# Page09_eMMC_QSPI.net
KiCad netlist of a schematic drawn in Altium Designer
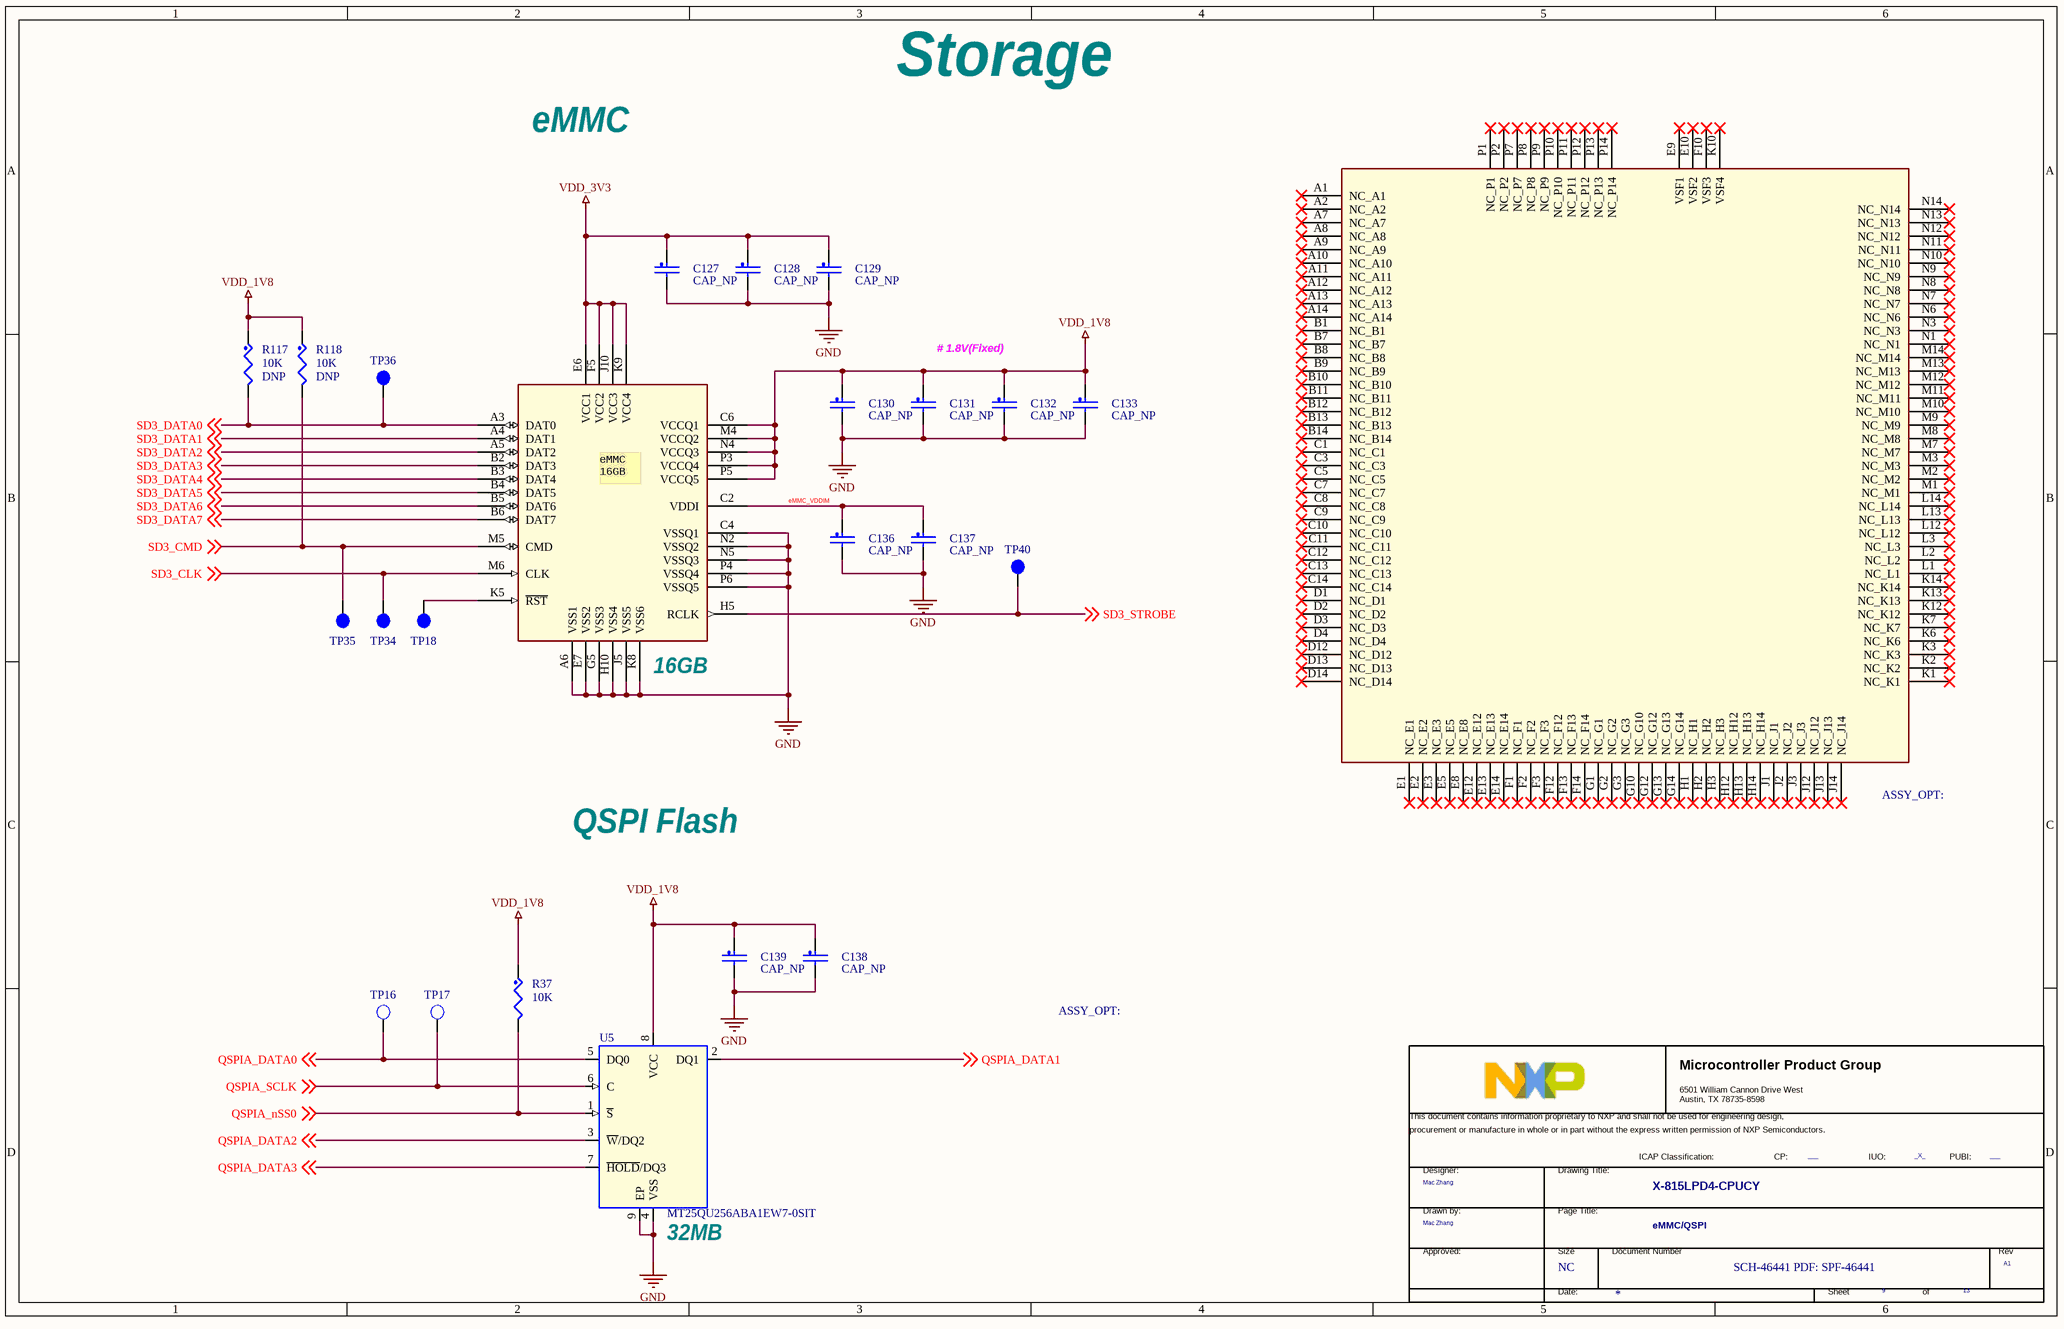
[diagram p0: Page09 eMMC_QSPI.SchDoc]

(export (version "E")
  (design (tool "Eeschema 10.0.6"))
  (components
    (comp (ref "C127") (value "CAP_NP") (footprint "RC0402") (libsource (lib "imx8mnano") (part "CAP_NP")))
    (comp (ref "C128") (value "CAP_NP") (footprint "RC0402") (libsource (lib "imx8mnano") (part "CAP_NP")))
    (comp (ref "C129") (value "CAP_NP") (footprint "RC0402") (libsource (lib "imx8mnano") (part "CAP_NP")))
    (comp (ref "C130") (value "CAP_NP") (footprint "RC0402") (libsource (lib "imx8mnano") (part "CAP_NP")))
    (comp (ref "C131") (value "CAP_NP") (footprint "RC0402") (libsource (lib "imx8mnano") (part "CAP_NP")))
    (comp (ref "C132") (value "CAP_NP") (footprint "RC0402") (libsource (lib "imx8mnano") (part "CAP_NP")))
    (comp (ref "C133") (value "CAP_NP") (footprint "RC0402") (libsource (lib "imx8mnano") (part "CAP_NP")))
    (comp (ref "C136") (value "CAP_NP") (footprint "RC0402") (libsource (lib "imx8mnano") (part "CAP_NP")))
    (comp (ref "C137") (value "CAP_NP") (footprint "RC0402") (libsource (lib "imx8mnano") (part "CAP_NP")))
    (comp (ref "C138") (value "CAP_NP") (footprint "RC0402") (libsource (lib "imx8mnano") (part "CAP_NP")))
    (comp (ref "C139") (value "CAP_NP") (footprint "RC0402") (libsource (lib "imx8mnano") (part "CAP_NP")))
    (comp (ref "R37")
      (value "10K")
      (footprint "0402_CC")
      (description "RES MF 10K 1/16W 5% 0402")
      (fields (field (name "TOLERANCE") "5%"))
      (libsource (lib "*") (part "RES"))
    )
    (comp (ref "R117")
      (value "10K")
      (footprint "0201_CC")
      (description "RES MF 10K 1/20W 5% 0201")
      (fields (field (name "ASSY_OPT") "DNP") (field (name "TOLERANCE") "5%"))
      (libsource (lib "*") (part "RES"))
    )
    (comp (ref "R118")
      (value "10K")
      (footprint "0201_CC")
      (description "RES MF 10K 1/20W 5% 0201")
      (fields (field (name "ASSY_OPT") "DNP") (field (name "TOLERANCE") "5%"))
      (libsource (lib "*") (part "RES"))
    )
    (comp (ref "TP16")
      (value "TP_35MIL")
      (footprint "testpoint_35mil")
      (description "TEST POINT PAD .035 SMT, no part to order")
      (libsource (lib "*") (part "T POINT R"))
    )
    (comp (ref "TP17")
      (value "TP_35MIL")
      (footprint "testpoint_35mil")
      (description "TEST POINT PAD .035 SMT, no part to order")
      (libsource (lib "*") (part "T POINT R"))
    )
    (comp (ref "TP18")
      (value "tpad_020")
      (footprint "tpad_020")
      (description "TEST POINT PAD 0.5MM DIA SMT, NO PART TO ORDER")
      (libsource (lib "*") (part "TESTLOOP"))
    )
    (comp (ref "TP34")
      (value "tpad_020")
      (footprint "tpad_020")
      (description "TEST POINT PAD 0.5MM DIA SMT, NO PART TO ORDER")
      (libsource (lib "*") (part "TESTLOOP"))
    )
    (comp (ref "TP35")
      (value "TPAD_015")
      (footprint "TPAD_015")
      (description "TEST POINT PAD 15MIL DIA SMT, NO PART TO ORDER")
      (libsource (lib "*") (part "TESTLOOP"))
    )
    (comp (ref "TP36")
      (value "tpad_020")
      (footprint "tpad_020")
      (description "TEST POINT PAD 0.5MM DIA SMT, NO PART TO ORDER")
      (libsource (lib "*") (part "TESTLOOP"))
    )
    (comp (ref "TP40")
      (value "TPAD_015")
      (footprint "TPAD_015")
      (description "TEST POINT PAD 15MIL DIA SMT, NO PART TO ORDER")
      (libsource (lib "*") (part "TESTLOOP"))
    )
    (comp (ref "U4")
      (value "SDINBDG4-16G_VFBGA_153P")
      (footprint "BGA153N50P14X14_1300X1150X80")
      (libsource (lib "imx8mnano") (part "SDINBDG4-16G_VFBGA_153P"))
    )
    (comp (ref "U5")
      (value "MT25QU256ABA1EW7-0SIT")
      (footprint "dfn8_1p27_6x5mm_3p1")
      (description "IC MEM FLASH SERIAL NOR 256MBIT 166MHZ 1.7-2V WPDFN8")
      (fields (field (name "VOLTAGE") "1.7-2V"))
      (libsource (lib "*") (part "MT25QL256ABA1EW9_9P"))
    )
  )
  (nets
    (net (code "1") (name "/eMMC_VDDIM") (class "Default")
      (node (ref "C136") (pin "1") (pinfunction "1_1") (pintype "passive"))
      (node (ref "C137") (pin "1") (pinfunction "1_1") (pintype "passive"))
      (node (ref "U4") (pin "C2") (pinfunction "VDDI_C2") (pintype "power_in"))
    )
    (net (code "2") (name "GND") (class "Default")
      (node (ref "C127") (pin "2") (pinfunction "2_2") (pintype "passive"))
      (node (ref "C128") (pin "2") (pinfunction "2_2") (pintype "passive"))
      (node (ref "C129") (pin "2") (pinfunction "2_2") (pintype "passive"))
      (node (ref "C130") (pin "2") (pinfunction "2_2") (pintype "passive"))
      (node (ref "C131") (pin "2") (pinfunction "2_2") (pintype "passive"))
      (node (ref "C132") (pin "2") (pinfunction "2_2") (pintype "passive"))
      (node (ref "C133") (pin "2") (pinfunction "2_2") (pintype "passive"))
      (node (ref "C136") (pin "2") (pinfunction "2_2") (pintype "passive"))
      (node (ref "C137") (pin "2") (pinfunction "2_2") (pintype "passive"))
      (node (ref "C138") (pin "2") (pinfunction "2_2") (pintype "passive"))
      (node (ref "C139") (pin "2") (pinfunction "2_2") (pintype "passive"))
      (node (ref "U4") (pin "A6") (pinfunction "VSS1_A6") (pintype "power_in"))
      (node (ref "U4") (pin "C4") (pinfunction "VSSQ1_C4") (pintype "power_in"))
      (node (ref "U4") (pin "E7") (pinfunction "VSS2_E7") (pintype "power_in"))
      (node (ref "U4") (pin "G5") (pinfunction "VSS3_G5") (pintype "power_in"))
      (node (ref "U4") (pin "H10") (pinfunction "VSS4_H10") (pintype "power_in"))
      (node (ref "U4") (pin "J5") (pinfunction "VSS5_J5") (pintype "power_in"))
      (node (ref "U4") (pin "K8") (pinfunction "VSS6_K8") (pintype "power_in"))
      (node (ref "U4") (pin "N2") (pinfunction "VSSQ2_N2") (pintype "power_in"))
      (node (ref "U4") (pin "N5") (pinfunction "VSSQ3_N5") (pintype "power_in"))
      (node (ref "U4") (pin "P4") (pinfunction "VSSQ4_P4") (pintype "power_in"))
      (node (ref "U4") (pin "P6") (pinfunction "VSSQ5_P6") (pintype "power_in"))
      (node (ref "U5") (pin "4") (pinfunction "VSS_4") (pintype "power_in"))
      (node (ref "U5") (pin "9") (pinfunction "EP_9") (pintype "power_in"))
    )
    (net (code "3") (name "Net-(TP18-Pin1)") (class "Default")
      (node (ref "TP18") (pin "1") (pinfunction "Pin1_1") (pintype "passive"))
      (node (ref "U4") (pin "K5") (pinfunction "~{RST}_K5") (pintype "input"))
    )
    (net (code "4") (name "QSPIA_DATA0") (class "Default")
      (node (ref "TP16") (pin "1") (pinfunction "TP_1") (pintype "passive"))
      (node (ref "U5") (pin "5") (pinfunction "DQ0_5") (pintype "bidirectional"))
    )
    (net (code "5") (name "QSPIA_DATA1") (class "Default")
      (node (ref "U5") (pin "2") (pinfunction "DQ1_2") (pintype "bidirectional"))
    )
    (net (code "6") (name "QSPIA_DATA2") (class "Default")
      (node (ref "U5") (pin "3") (pinfunction "~{W}/DQ2_3") (pintype "bidirectional"))
    )
    (net (code "7") (name "QSPIA_DATA3") (class "Default")
      (node (ref "U5") (pin "7") (pinfunction "~{HOLD}/DQ3_7") (pintype "bidirectional"))
    )
    (net (code "8") (name "QSPIA_SCLK") (class "Default")
      (node (ref "TP17") (pin "1") (pinfunction "TP_1") (pintype "passive"))
      (node (ref "U5") (pin "6") (pinfunction "C_6") (pintype "input"))
    )
    (net (code "9") (name "QSPIA_nSS0") (class "Default")
      (node (ref "R37") (pin "2") (pinfunction "2_2") (pintype "passive"))
      (node (ref "U5") (pin "1") (pinfunction "~{S}_1") (pintype "input"))
    )
    (net (code "10") (name "SD3_CLK") (class "Default")
      (node (ref "TP34") (pin "1") (pinfunction "Pin1_1") (pintype "passive"))
      (node (ref "U4") (pin "M6") (pinfunction "CLK_M6") (pintype "input"))
    )
    (net (code "11") (name "SD3_CMD") (class "Default")
      (node (ref "R118") (pin "2") (pinfunction "2_2") (pintype "passive"))
      (node (ref "TP35") (pin "1") (pinfunction "Pin1_1") (pintype "passive"))
      (node (ref "U4") (pin "M5") (pinfunction "CMD_M5") (pintype "bidirectional"))
    )
    (net (code "12") (name "SD3_DATA0") (class "Default")
      (node (ref "R117") (pin "2") (pinfunction "2_2") (pintype "passive"))
      (node (ref "TP36") (pin "1") (pinfunction "Pin1_1") (pintype "passive"))
      (node (ref "U4") (pin "A3") (pinfunction "DAT0_A3") (pintype "bidirectional"))
    )
    (net (code "13") (name "SD3_DATA1") (class "Default")
      (node (ref "U4") (pin "A4") (pinfunction "DAT1_A4") (pintype "bidirectional"))
    )
    (net (code "14") (name "SD3_DATA2") (class "Default")
      (node (ref "U4") (pin "A5") (pinfunction "DAT2_A5") (pintype "bidirectional"))
    )
    (net (code "15") (name "SD3_DATA3") (class "Default")
      (node (ref "U4") (pin "B2") (pinfunction "DAT3_B2") (pintype "bidirectional"))
    )
    (net (code "16") (name "SD3_DATA4") (class "Default")
      (node (ref "U4") (pin "B3") (pinfunction "DAT4_B3") (pintype "bidirectional"))
    )
    (net (code "17") (name "SD3_DATA5") (class "Default")
      (node (ref "U4") (pin "B4") (pinfunction "DAT5_B4") (pintype "bidirectional"))
    )
    (net (code "18") (name "SD3_DATA6") (class "Default")
      (node (ref "U4") (pin "B5") (pinfunction "DAT6_B5") (pintype "bidirectional"))
    )
    (net (code "19") (name "SD3_DATA7") (class "Default")
      (node (ref "U4") (pin "B6") (pinfunction "DAT7_B6") (pintype "bidirectional"))
    )
    (net (code "20") (name "SD3_STROBE") (class "Default")
      (node (ref "TP40") (pin "1") (pinfunction "Pin1_1") (pintype "passive"))
      (node (ref "U4") (pin "H5") (pinfunction "RCLK_H5") (pintype "output"))
    )
    (net (code "21") (name "VDD_1V8") (class "Default")
      (node (ref "C130") (pin "1") (pinfunction "1_1") (pintype "passive"))
      (node (ref "C131") (pin "1") (pinfunction "1_1") (pintype "passive"))
      (node (ref "C132") (pin "1") (pinfunction "1_1") (pintype "passive"))
      (node (ref "C133") (pin "1") (pinfunction "1_1") (pintype "passive"))
      (node (ref "C138") (pin "1") (pinfunction "1_1") (pintype "passive"))
      (node (ref "C139") (pin "1") (pinfunction "1_1") (pintype "passive"))
      (node (ref "R117") (pin "1") (pinfunction "1_1") (pintype "passive"))
      (node (ref "R118") (pin "1") (pinfunction "1_1") (pintype "passive"))
      (node (ref "R37") (pin "1") (pinfunction "1_1") (pintype "passive"))
      (node (ref "U4") (pin "C6") (pinfunction "VCCQ1_C6") (pintype "power_in"))
      (node (ref "U4") (pin "M4") (pinfunction "VCCQ2_M4") (pintype "power_in"))
      (node (ref "U4") (pin "N4") (pinfunction "VCCQ3_N4") (pintype "power_in"))
      (node (ref "U4") (pin "P3") (pinfunction "VCCQ4_P3") (pintype "power_in"))
      (node (ref "U4") (pin "P5") (pinfunction "VCCQ5_P5") (pintype "power_in"))
      (node (ref "U5") (pin "8") (pinfunction "VCC_8") (pintype "power_in"))
    )
    (net (code "22") (name "VDD_3V3") (class "Default")
      (node (ref "C127") (pin "1") (pinfunction "1_1") (pintype "passive"))
      (node (ref "C128") (pin "1") (pinfunction "1_1") (pintype "passive"))
      (node (ref "C129") (pin "1") (pinfunction "1_1") (pintype "passive"))
      (node (ref "U4") (pin "E6") (pinfunction "VCC1_E6") (pintype "power_in"))
      (node (ref "U4") (pin "F5") (pinfunction "VCC2_F5") (pintype "power_in"))
      (node (ref "U4") (pin "J10") (pinfunction "VCC3_J10") (pintype "power_in"))
      (node (ref "U4") (pin "K9") (pinfunction "VCC4_K9") (pintype "power_in"))
    )
    (net (code "23") (name "unconnected-(U4B-NC_A1-PadA1)") (class "Default")
      (node (ref "U4") (pin "A1") (pinfunction "NC_A1_A1") (pintype "passive+no_connect"))
    )
    (net (code "24") (name "unconnected-(U4B-NC_A2-PadA2)") (class "Default")
      (node (ref "U4") (pin "A2") (pinfunction "NC_A2_A2") (pintype "passive+no_connect"))
    )
    (net (code "25") (name "unconnected-(U4B-NC_A7-PadA7)") (class "Default")
      (node (ref "U4") (pin "A7") (pinfunction "NC_A7_A7") (pintype "passive+no_connect"))
    )
    (net (code "26") (name "unconnected-(U4B-NC_A8-PadA8)") (class "Default")
      (node (ref "U4") (pin "A8") (pinfunction "NC_A8_A8") (pintype "passive+no_connect"))
    )
    (net (code "27") (name "unconnected-(U4B-NC_A9-PadA9)") (class "Default")
      (node (ref "U4") (pin "A9") (pinfunction "NC_A9_A9") (pintype "passive+no_connect"))
    )
    (net (code "28") (name "unconnected-(U4B-NC_A10-PadA10)") (class "Default")
      (node (ref "U4") (pin "A10") (pinfunction "NC_A10_A10") (pintype "passive+no_connect"))
    )
    (net (code "29") (name "unconnected-(U4B-NC_A11-PadA11)") (class "Default")
      (node (ref "U4") (pin "A11") (pinfunction "NC_A11_A11") (pintype "passive+no_connect"))
    )
    (net (code "30") (name "unconnected-(U4B-NC_A12-PadA12)") (class "Default")
      (node (ref "U4") (pin "A12") (pinfunction "NC_A12_A12") (pintype "passive+no_connect"))
    )
    (net (code "31") (name "unconnected-(U4B-NC_A13-PadA13)") (class "Default")
      (node (ref "U4") (pin "A13") (pinfunction "NC_A13_A13") (pintype "passive+no_connect"))
    )
    (net (code "32") (name "unconnected-(U4B-NC_A14-PadA14)") (class "Default")
      (node (ref "U4") (pin "A14") (pinfunction "NC_A14_A14") (pintype "passive+no_connect"))
    )
    (net (code "33") (name "unconnected-(U4B-NC_B1-PadB1)") (class "Default")
      (node (ref "U4") (pin "B1") (pinfunction "NC_B1_B1") (pintype "passive+no_connect"))
    )
    (net (code "34") (name "unconnected-(U4B-NC_B7-PadB7)") (class "Default")
      (node (ref "U4") (pin "B7") (pinfunction "NC_B7_B7") (pintype "passive+no_connect"))
    )
    (net (code "35") (name "unconnected-(U4B-NC_B8-PadB8)") (class "Default")
      (node (ref "U4") (pin "B8") (pinfunction "NC_B8_B8") (pintype "passive+no_connect"))
    )
    (net (code "36") (name "unconnected-(U4B-NC_B9-PadB9)") (class "Default")
      (node (ref "U4") (pin "B9") (pinfunction "NC_B9_B9") (pintype "passive+no_connect"))
    )
    (net (code "37") (name "unconnected-(U4B-NC_B10-PadB10)") (class "Default")
      (node (ref "U4") (pin "B10") (pinfunction "NC_B10_B10") (pintype "passive+no_connect"))
    )
    (net (code "38") (name "unconnected-(U4B-NC_B11-PadB11)") (class "Default")
      (node (ref "U4") (pin "B11") (pinfunction "NC_B11_B11") (pintype "passive+no_connect"))
    )
    (net (code "39") (name "unconnected-(U4B-NC_B12-PadB12)") (class "Default")
      (node (ref "U4") (pin "B12") (pinfunction "NC_B12_B12") (pintype "passive+no_connect"))
    )
    (net (code "40") (name "unconnected-(U4B-NC_B13-PadB13)") (class "Default")
      (node (ref "U4") (pin "B13") (pinfunction "NC_B13_B13") (pintype "passive+no_connect"))
    )
    (net (code "41") (name "unconnected-(U4B-NC_B14-PadB14)") (class "Default")
      (node (ref "U4") (pin "B14") (pinfunction "NC_B14_B14") (pintype "passive+no_connect"))
    )
    (net (code "42") (name "unconnected-(U4B-NC_C1-PadC1)") (class "Default")
      (node (ref "U4") (pin "C1") (pinfunction "NC_C1_C1") (pintype "passive+no_connect"))
    )
    (net (code "43") (name "unconnected-(U4B-NC_C3-PadC3)") (class "Default")
      (node (ref "U4") (pin "C3") (pinfunction "NC_C3_C3") (pintype "passive+no_connect"))
    )
    (net (code "44") (name "unconnected-(U4B-NC_C5-PadC5)") (class "Default")
      (node (ref "U4") (pin "C5") (pinfunction "NC_C5_C5") (pintype "passive+no_connect"))
    )
    (net (code "45") (name "unconnected-(U4B-NC_C7-PadC7)") (class "Default")
      (node (ref "U4") (pin "C7") (pinfunction "NC_C7_C7") (pintype "passive+no_connect"))
    )
    (net (code "46") (name "unconnected-(U4B-NC_C8-PadC8)") (class "Default")
      (node (ref "U4") (pin "C8") (pinfunction "NC_C8_C8") (pintype "passive+no_connect"))
    )
    (net (code "47") (name "unconnected-(U4B-NC_C9-PadC9)") (class "Default")
      (node (ref "U4") (pin "C9") (pinfunction "NC_C9_C9") (pintype "passive+no_connect"))
    )
    (net (code "48") (name "unconnected-(U4B-NC_C10-PadC10)") (class "Default")
      (node (ref "U4") (pin "C10") (pinfunction "NC_C10_C10") (pintype "passive+no_connect"))
    )
    (net (code "49") (name "unconnected-(U4B-NC_C11-PadC11)") (class "Default")
      (node (ref "U4") (pin "C11") (pinfunction "NC_C11_C11") (pintype "passive+no_connect"))
    )
    (net (code "50") (name "unconnected-(U4B-NC_C12-PadC12)") (class "Default")
      (node (ref "U4") (pin "C12") (pinfunction "NC_C12_C12") (pintype "passive+no_connect"))
    )
    (net (code "51") (name "unconnected-(U4B-NC_C13-PadC13)") (class "Default")
      (node (ref "U4") (pin "C13") (pinfunction "NC_C13_C13") (pintype "passive+no_connect"))
    )
    (net (code "52") (name "unconnected-(U4B-NC_C14-PadC14)") (class "Default")
      (node (ref "U4") (pin "C14") (pinfunction "NC_C14_C14") (pintype "passive+no_connect"))
    )
    (net (code "53") (name "unconnected-(U4B-NC_D1-PadD1)") (class "Default")
      (node (ref "U4") (pin "D1") (pinfunction "NC_D1_D1") (pintype "passive+no_connect"))
    )
    (net (code "54") (name "unconnected-(U4B-NC_D2-PadD2)") (class "Default")
      (node (ref "U4") (pin "D2") (pinfunction "NC_D2_D2") (pintype "passive+no_connect"))
    )
    (net (code "55") (name "unconnected-(U4B-NC_D3-PadD3)") (class "Default")
      (node (ref "U4") (pin "D3") (pinfunction "NC_D3_D3") (pintype "passive+no_connect"))
    )
    (net (code "56") (name "unconnected-(U4B-NC_D4-PadD4)") (class "Default")
      (node (ref "U4") (pin "D4") (pinfunction "NC_D4_D4") (pintype "passive+no_connect"))
    )
    (net (code "57") (name "unconnected-(U4B-NC_D12-PadD12)") (class "Default")
      (node (ref "U4") (pin "D12") (pinfunction "NC_D12_D12") (pintype "passive+no_connect"))
    )
    (net (code "58") (name "unconnected-(U4B-NC_D13-PadD13)") (class "Default")
      (node (ref "U4") (pin "D13") (pinfunction "NC_D13_D13") (pintype "passive+no_connect"))
    )
    (net (code "59") (name "unconnected-(U4B-NC_D14-PadD14)") (class "Default")
      (node (ref "U4") (pin "D14") (pinfunction "NC_D14_D14") (pintype "passive+no_connect"))
    )
    (net (code "60") (name "unconnected-(U4B-NC_E1-PadE1)") (class "Default")
      (node (ref "U4") (pin "E1") (pinfunction "NC_E1_E1") (pintype "passive+no_connect"))
    )
    (net (code "61") (name "unconnected-(U4B-NC_E2-PadE2)") (class "Default")
      (node (ref "U4") (pin "E2") (pinfunction "NC_E2_E2") (pintype "passive+no_connect"))
    )
    (net (code "62") (name "unconnected-(U4B-NC_E3-PadE3)") (class "Default")
      (node (ref "U4") (pin "E3") (pinfunction "NC_E3_E3") (pintype "passive+no_connect"))
    )
    (net (code "63") (name "unconnected-(U4B-NC_E5-PadE5)") (class "Default")
      (node (ref "U4") (pin "E5") (pinfunction "NC_E5_E5") (pintype "passive+no_connect"))
    )
    (net (code "64") (name "unconnected-(U4B-NC_E8-PadE8)") (class "Default")
      (node (ref "U4") (pin "E8") (pinfunction "NC_E8_E8") (pintype "passive+no_connect"))
    )
    (net (code "65") (name "unconnected-(U4B-NC_E12-PadE12)") (class "Default")
      (node (ref "U4") (pin "E12") (pinfunction "NC_E12_E12") (pintype "passive+no_connect"))
    )
    (net (code "66") (name "unconnected-(U4B-NC_E13-PadE13)") (class "Default")
      (node (ref "U4") (pin "E13") (pinfunction "NC_E13_E13") (pintype "passive+no_connect"))
    )
    (net (code "67") (name "unconnected-(U4B-NC_E14-PadE14)") (class "Default")
      (node (ref "U4") (pin "E14") (pinfunction "NC_E14_E14") (pintype "passive+no_connect"))
    )
    (net (code "68") (name "unconnected-(U4B-NC_F1-PadF1)") (class "Default")
      (node (ref "U4") (pin "F1") (pinfunction "NC_F1_F1") (pintype "passive+no_connect"))
    )
    (net (code "69") (name "unconnected-(U4B-NC_F2-PadF2)") (class "Default")
      (node (ref "U4") (pin "F2") (pinfunction "NC_F2_F2") (pintype "passive+no_connect"))
    )
    (net (code "70") (name "unconnected-(U4B-NC_F3-PadF3)") (class "Default")
      (node (ref "U4") (pin "F3") (pinfunction "NC_F3_F3") (pintype "passive+no_connect"))
    )
    (net (code "71") (name "unconnected-(U4B-NC_F12-PadF12)") (class "Default")
      (node (ref "U4") (pin "F12") (pinfunction "NC_F12_F12") (pintype "passive+no_connect"))
    )
    (net (code "72") (name "unconnected-(U4B-NC_F13-PadF13)") (class "Default")
      (node (ref "U4") (pin "F13") (pinfunction "NC_F13_F13") (pintype "passive+no_connect"))
    )
    (net (code "73") (name "unconnected-(U4B-NC_F14-PadF14)") (class "Default")
      (node (ref "U4") (pin "F14") (pinfunction "NC_F14_F14") (pintype "passive+no_connect"))
    )
    (net (code "74") (name "unconnected-(U4B-NC_G1-PadG1)") (class "Default")
      (node (ref "U4") (pin "G1") (pinfunction "NC_G1_G1") (pintype "passive+no_connect"))
    )
    (net (code "75") (name "unconnected-(U4B-NC_G2-PadG2)") (class "Default")
      (node (ref "U4") (pin "G2") (pinfunction "NC_G2_G2") (pintype "passive+no_connect"))
    )
    (net (code "76") (name "unconnected-(U4B-NC_G3-PadG3)") (class "Default")
      (node (ref "U4") (pin "G3") (pinfunction "NC_G3_G3") (pintype "passive+no_connect"))
    )
    (net (code "77") (name "unconnected-(U4B-NC_G10-PadG10)") (class "Default")
      (node (ref "U4") (pin "G10") (pinfunction "NC_G10_G10") (pintype "passive+no_connect"))
    )
    (net (code "78") (name "unconnected-(U4B-NC_G12-PadG12)") (class "Default")
      (node (ref "U4") (pin "G12") (pinfunction "NC_G12_G12") (pintype "passive+no_connect"))
    )
    (net (code "79") (name "unconnected-(U4B-NC_G13-PadG13)") (class "Default")
      (node (ref "U4") (pin "G13") (pinfunction "NC_G13_G13") (pintype "passive+no_connect"))
    )
    (net (code "80") (name "unconnected-(U4B-NC_G14-PadG14)") (class "Default")
      (node (ref "U4") (pin "G14") (pinfunction "NC_G14_G14") (pintype "passive+no_connect"))
    )
    (net (code "81") (name "unconnected-(U4B-NC_H1-PadH1)") (class "Default")
      (node (ref "U4") (pin "H1") (pinfunction "NC_H1_H1") (pintype "passive+no_connect"))
    )
    (net (code "82") (name "unconnected-(U4B-NC_H2-PadH2)") (class "Default")
      (node (ref "U4") (pin "H2") (pinfunction "NC_H2_H2") (pintype "passive+no_connect"))
    )
    (net (code "83") (name "unconnected-(U4B-NC_H3-PadH3)") (class "Default")
      (node (ref "U4") (pin "H3") (pinfunction "NC_H3_H3") (pintype "passive+no_connect"))
    )
    (net (code "84") (name "unconnected-(U4B-NC_H12-PadH12)") (class "Default")
      (node (ref "U4") (pin "H12") (pinfunction "NC_H12_H12") (pintype "passive+no_connect"))
    )
    (net (code "85") (name "unconnected-(U4B-NC_H13-PadH13)") (class "Default")
      (node (ref "U4") (pin "H13") (pinfunction "NC_H13_H13") (pintype "passive+no_connect"))
    )
    (net (code "86") (name "unconnected-(U4B-NC_H14-PadH14)") (class "Default")
      (node (ref "U4") (pin "H14") (pinfunction "NC_H14_H14") (pintype "passive+no_connect"))
    )
    (net (code "87") (name "unconnected-(U4B-NC_J1-PadJ1)") (class "Default")
      (node (ref "U4") (pin "J1") (pinfunction "NC_J1_J1") (pintype "passive+no_connect"))
    )
    (net (code "88") (name "unconnected-(U4B-NC_J2-PadJ2)") (class "Default")
      (node (ref "U4") (pin "J2") (pinfunction "NC_J2_J2") (pintype "passive+no_connect"))
    )
    (net (code "89") (name "unconnected-(U4B-NC_J3-PadJ3)") (class "Default")
      (node (ref "U4") (pin "J3") (pinfunction "NC_J3_J3") (pintype "passive+no_connect"))
    )
    (net (code "90") (name "unconnected-(U4B-NC_J12-PadJ12)") (class "Default")
      (node (ref "U4") (pin "J12") (pinfunction "NC_J12_J12") (pintype "passive+no_connect"))
    )
    (net (code "91") (name "unconnected-(U4B-NC_J13-PadJ13)") (class "Default")
      (node (ref "U4") (pin "J13") (pinfunction "NC_J13_J13") (pintype "passive+no_connect"))
    )
    (net (code "92") (name "unconnected-(U4B-NC_J14-PadJ14)") (class "Default")
      (node (ref "U4") (pin "J14") (pinfunction "NC_J14_J14") (pintype "passive+no_connect"))
    )
    (net (code "93") (name "unconnected-(U4B-NC_K1-PadK1)") (class "Default")
      (node (ref "U4") (pin "K1") (pinfunction "NC_K1_K1") (pintype "passive+no_connect"))
    )
    (net (code "94") (name "unconnected-(U4B-NC_K2-PadK2)") (class "Default")
      (node (ref "U4") (pin "K2") (pinfunction "NC_K2_K2") (pintype "passive+no_connect"))
    )
    (net (code "95") (name "unconnected-(U4B-NC_K3-PadK3)") (class "Default")
      (node (ref "U4") (pin "K3") (pinfunction "NC_K3_K3") (pintype "passive+no_connect"))
    )
    (net (code "96") (name "unconnected-(U4B-NC_K6-PadK6)") (class "Default")
      (node (ref "U4") (pin "K6") (pinfunction "NC_K6_K6") (pintype "passive+no_connect"))
    )
    (net (code "97") (name "unconnected-(U4B-NC_K7-PadK7)") (class "Default")
      (node (ref "U4") (pin "K7") (pinfunction "NC_K7_K7") (pintype "passive+no_connect"))
    )
    (net (code "98") (name "unconnected-(U4B-NC_K12-PadK12)") (class "Default")
      (node (ref "U4") (pin "K12") (pinfunction "NC_K12_K12") (pintype "passive+no_connect"))
    )
    (net (code "99") (name "unconnected-(U4B-NC_K13-PadK13)") (class "Default")
      (node (ref "U4") (pin "K13") (pinfunction "NC_K13_K13") (pintype "passive+no_connect"))
    )
    (net (code "100") (name "unconnected-(U4B-NC_K14-PadK14)") (class "Default")
      (node (ref "U4") (pin "K14") (pinfunction "NC_K14_K14") (pintype "passive+no_connect"))
    )
    (net (code "101") (name "unconnected-(U4B-NC_L1-PadL1)") (class "Default")
      (node (ref "U4") (pin "L1") (pinfunction "NC_L1_L1") (pintype "passive+no_connect"))
    )
    (net (code "102") (name "unconnected-(U4B-NC_L2-PadL2)") (class "Default")
      (node (ref "U4") (pin "L2") (pinfunction "NC_L2_L2") (pintype "passive+no_connect"))
    )
    (net (code "103") (name "unconnected-(U4B-NC_L3-PadL3)") (class "Default")
      (node (ref "U4") (pin "L3") (pinfunction "NC_L3_L3") (pintype "passive+no_connect"))
    )
    (net (code "104") (name "unconnected-(U4B-NC_L12-PadL12)") (class "Default")
      (node (ref "U4") (pin "L12") (pinfunction "NC_L12_L12") (pintype "passive+no_connect"))
    )
    (net (code "105") (name "unconnected-(U4B-NC_L13-PadL13)") (class "Default")
      (node (ref "U4") (pin "L13") (pinfunction "NC_L13_L13") (pintype "passive+no_connect"))
    )
    (net (code "106") (name "unconnected-(U4B-NC_L14-PadL14)") (class "Default")
      (node (ref "U4") (pin "L14") (pinfunction "NC_L14_L14") (pintype "passive+no_connect"))
    )
    (net (code "107") (name "unconnected-(U4B-NC_M1-PadM1)") (class "Default")
      (node (ref "U4") (pin "M1") (pinfunction "NC_M1_M1") (pintype "passive+no_connect"))
    )
    (net (code "108") (name "unconnected-(U4B-NC_M2-PadM2)") (class "Default")
      (node (ref "U4") (pin "M2") (pinfunction "NC_M2_M2") (pintype "passive+no_connect"))
    )
    (net (code "109") (name "unconnected-(U4B-NC_M3-PadM3)") (class "Default")
      (node (ref "U4") (pin "M3") (pinfunction "NC_M3_M3") (pintype "passive+no_connect"))
    )
    (net (code "110") (name "unconnected-(U4B-NC_M7-PadM7)") (class "Default")
      (node (ref "U4") (pin "M7") (pinfunction "NC_M7_M7") (pintype "passive+no_connect"))
    )
    (net (code "111") (name "unconnected-(U4B-NC_M8-PadM8)") (class "Default")
      (node (ref "U4") (pin "M8") (pinfunction "NC_M8_M8") (pintype "passive+no_connect"))
    )
    (net (code "112") (name "unconnected-(U4B-NC_M9-PadM9)") (class "Default")
      (node (ref "U4") (pin "M9") (pinfunction "NC_M9_M9") (pintype "passive+no_connect"))
    )
    (net (code "113") (name "unconnected-(U4B-NC_M10-PadM10)") (class "Default")
      (node (ref "U4") (pin "M10") (pinfunction "NC_M10_M10") (pintype "passive+no_connect"))
    )
    (net (code "114") (name "unconnected-(U4B-NC_M11-PadM11)") (class "Default")
      (node (ref "U4") (pin "M11") (pinfunction "NC_M11_M11") (pintype "passive+no_connect"))
    )
    (net (code "115") (name "unconnected-(U4B-NC_M12-PadM12)") (class "Default")
      (node (ref "U4") (pin "M12") (pinfunction "NC_M12_M12") (pintype "passive+no_connect"))
    )
    (net (code "116") (name "unconnected-(U4B-NC_M13-PadM13)") (class "Default")
      (node (ref "U4") (pin "M13") (pinfunction "NC_M13_M13") (pintype "passive+no_connect"))
    )
    (net (code "117") (name "unconnected-(U4B-NC_M14-PadM14)") (class "Default")
      (node (ref "U4") (pin "M14") (pinfunction "NC_M14_M14") (pintype "passive+no_connect"))
    )
    (net (code "118") (name "unconnected-(U4B-NC_N1-PadN1)") (class "Default")
      (node (ref "U4") (pin "N1") (pinfunction "NC_N1_N1") (pintype "passive+no_connect"))
    )
    (net (code "119") (name "unconnected-(U4B-NC_N3-PadN3)") (class "Default")
      (node (ref "U4") (pin "N3") (pinfunction "NC_N3_N3") (pintype "passive+no_connect"))
    )
    (net (code "120") (name "unconnected-(U4B-NC_N6-PadN6)") (class "Default")
      (node (ref "U4") (pin "N6") (pinfunction "NC_N6_N6") (pintype "passive+no_connect"))
    )
    (net (code "121") (name "unconnected-(U4B-NC_N7-PadN7)") (class "Default")
      (node (ref "U4") (pin "N7") (pinfunction "NC_N7_N7") (pintype "passive+no_connect"))
    )
    (net (code "122") (name "unconnected-(U4B-NC_N8-PadN8)") (class "Default")
      (node (ref "U4") (pin "N8") (pinfunction "NC_N8_N8") (pintype "passive+no_connect"))
    )
    (net (code "123") (name "unconnected-(U4B-NC_N9-PadN9)") (class "Default")
      (node (ref "U4") (pin "N9") (pinfunction "NC_N9_N9") (pintype "passive+no_connect"))
    )
    (net (code "124") (name "unconnected-(U4B-NC_N10-PadN10)") (class "Default")
      (node (ref "U4") (pin "N10") (pinfunction "NC_N10_N10") (pintype "passive+no_connect"))
    )
    (net (code "125") (name "unconnected-(U4B-NC_N11-PadN11)") (class "Default")
      (node (ref "U4") (pin "N11") (pinfunction "NC_N11_N11") (pintype "passive+no_connect"))
    )
    (net (code "126") (name "unconnected-(U4B-NC_N12-PadN12)") (class "Default")
      (node (ref "U4") (pin "N12") (pinfunction "NC_N12_N12") (pintype "passive+no_connect"))
    )
    (net (code "127") (name "unconnected-(U4B-NC_N13-PadN13)") (class "Default")
      (node (ref "U4") (pin "N13") (pinfunction "NC_N13_N13") (pintype "passive+no_connect"))
    )
    (net (code "128") (name "unconnected-(U4B-NC_N14-PadN14)") (class "Default")
      (node (ref "U4") (pin "N14") (pinfunction "NC_N14_N14") (pintype "passive+no_connect"))
    )
    (net (code "129") (name "unconnected-(U4B-NC_P1-PadP1)") (class "Default")
      (node (ref "U4") (pin "P1") (pinfunction "NC_P1_P1") (pintype "passive+no_connect"))
    )
    (net (code "130") (name "unconnected-(U4B-NC_P2-PadP2)") (class "Default")
      (node (ref "U4") (pin "P2") (pinfunction "NC_P2_P2") (pintype "passive+no_connect"))
    )
    (net (code "131") (name "unconnected-(U4B-NC_P7-PadP7)") (class "Default")
      (node (ref "U4") (pin "P7") (pinfunction "NC_P7_P7") (pintype "passive+no_connect"))
    )
    (net (code "132") (name "unconnected-(U4B-NC_P8-PadP8)") (class "Default")
      (node (ref "U4") (pin "P8") (pinfunction "NC_P8_P8") (pintype "passive+no_connect"))
    )
    (net (code "133") (name "unconnected-(U4B-NC_P9-PadP9)") (class "Default")
      (node (ref "U4") (pin "P9") (pinfunction "NC_P9_P9") (pintype "passive+no_connect"))
    )
    (net (code "134") (name "unconnected-(U4B-NC_P10-PadP10)") (class "Default")
      (node (ref "U4") (pin "P10") (pinfunction "NC_P10_P10") (pintype "passive+no_connect"))
    )
    (net (code "135") (name "unconnected-(U4B-NC_P11-PadP11)") (class "Default")
      (node (ref "U4") (pin "P11") (pinfunction "NC_P11_P11") (pintype "passive+no_connect"))
    )
    (net (code "136") (name "unconnected-(U4B-NC_P12-PadP12)") (class "Default")
      (node (ref "U4") (pin "P12") (pinfunction "NC_P12_P12") (pintype "passive+no_connect"))
    )
    (net (code "137") (name "unconnected-(U4B-NC_P13-PadP13)") (class "Default")
      (node (ref "U4") (pin "P13") (pinfunction "NC_P13_P13") (pintype "passive+no_connect"))
    )
    (net (code "138") (name "unconnected-(U4B-NC_P14-PadP14)") (class "Default")
      (node (ref "U4") (pin "P14") (pinfunction "NC_P14_P14") (pintype "passive+no_connect"))
    )
    (net (code "139") (name "unconnected-(U4B-VSF1-PadE9)") (class "Default")
      (node (ref "U4") (pin "E9") (pinfunction "VSF1_E9") (pintype "passive+no_connect"))
    )
    (net (code "140") (name "unconnected-(U4B-VSF2-PadE10)") (class "Default")
      (node (ref "U4") (pin "E10") (pinfunction "VSF2_E10") (pintype "passive+no_connect"))
    )
    (net (code "141") (name "unconnected-(U4B-VSF3-PadF10)") (class "Default")
      (node (ref "U4") (pin "F10") (pinfunction "VSF3_F10") (pintype "passive+no_connect"))
    )
    (net (code "142") (name "unconnected-(U4B-VSF4-PadK10)") (class "Default")
      (node (ref "U4") (pin "K10") (pinfunction "VSF4_K10") (pintype "passive+no_connect"))
    )
  )
)
